# Xenon.net
KiCad netlist of a schematic drawn in Altium Designer
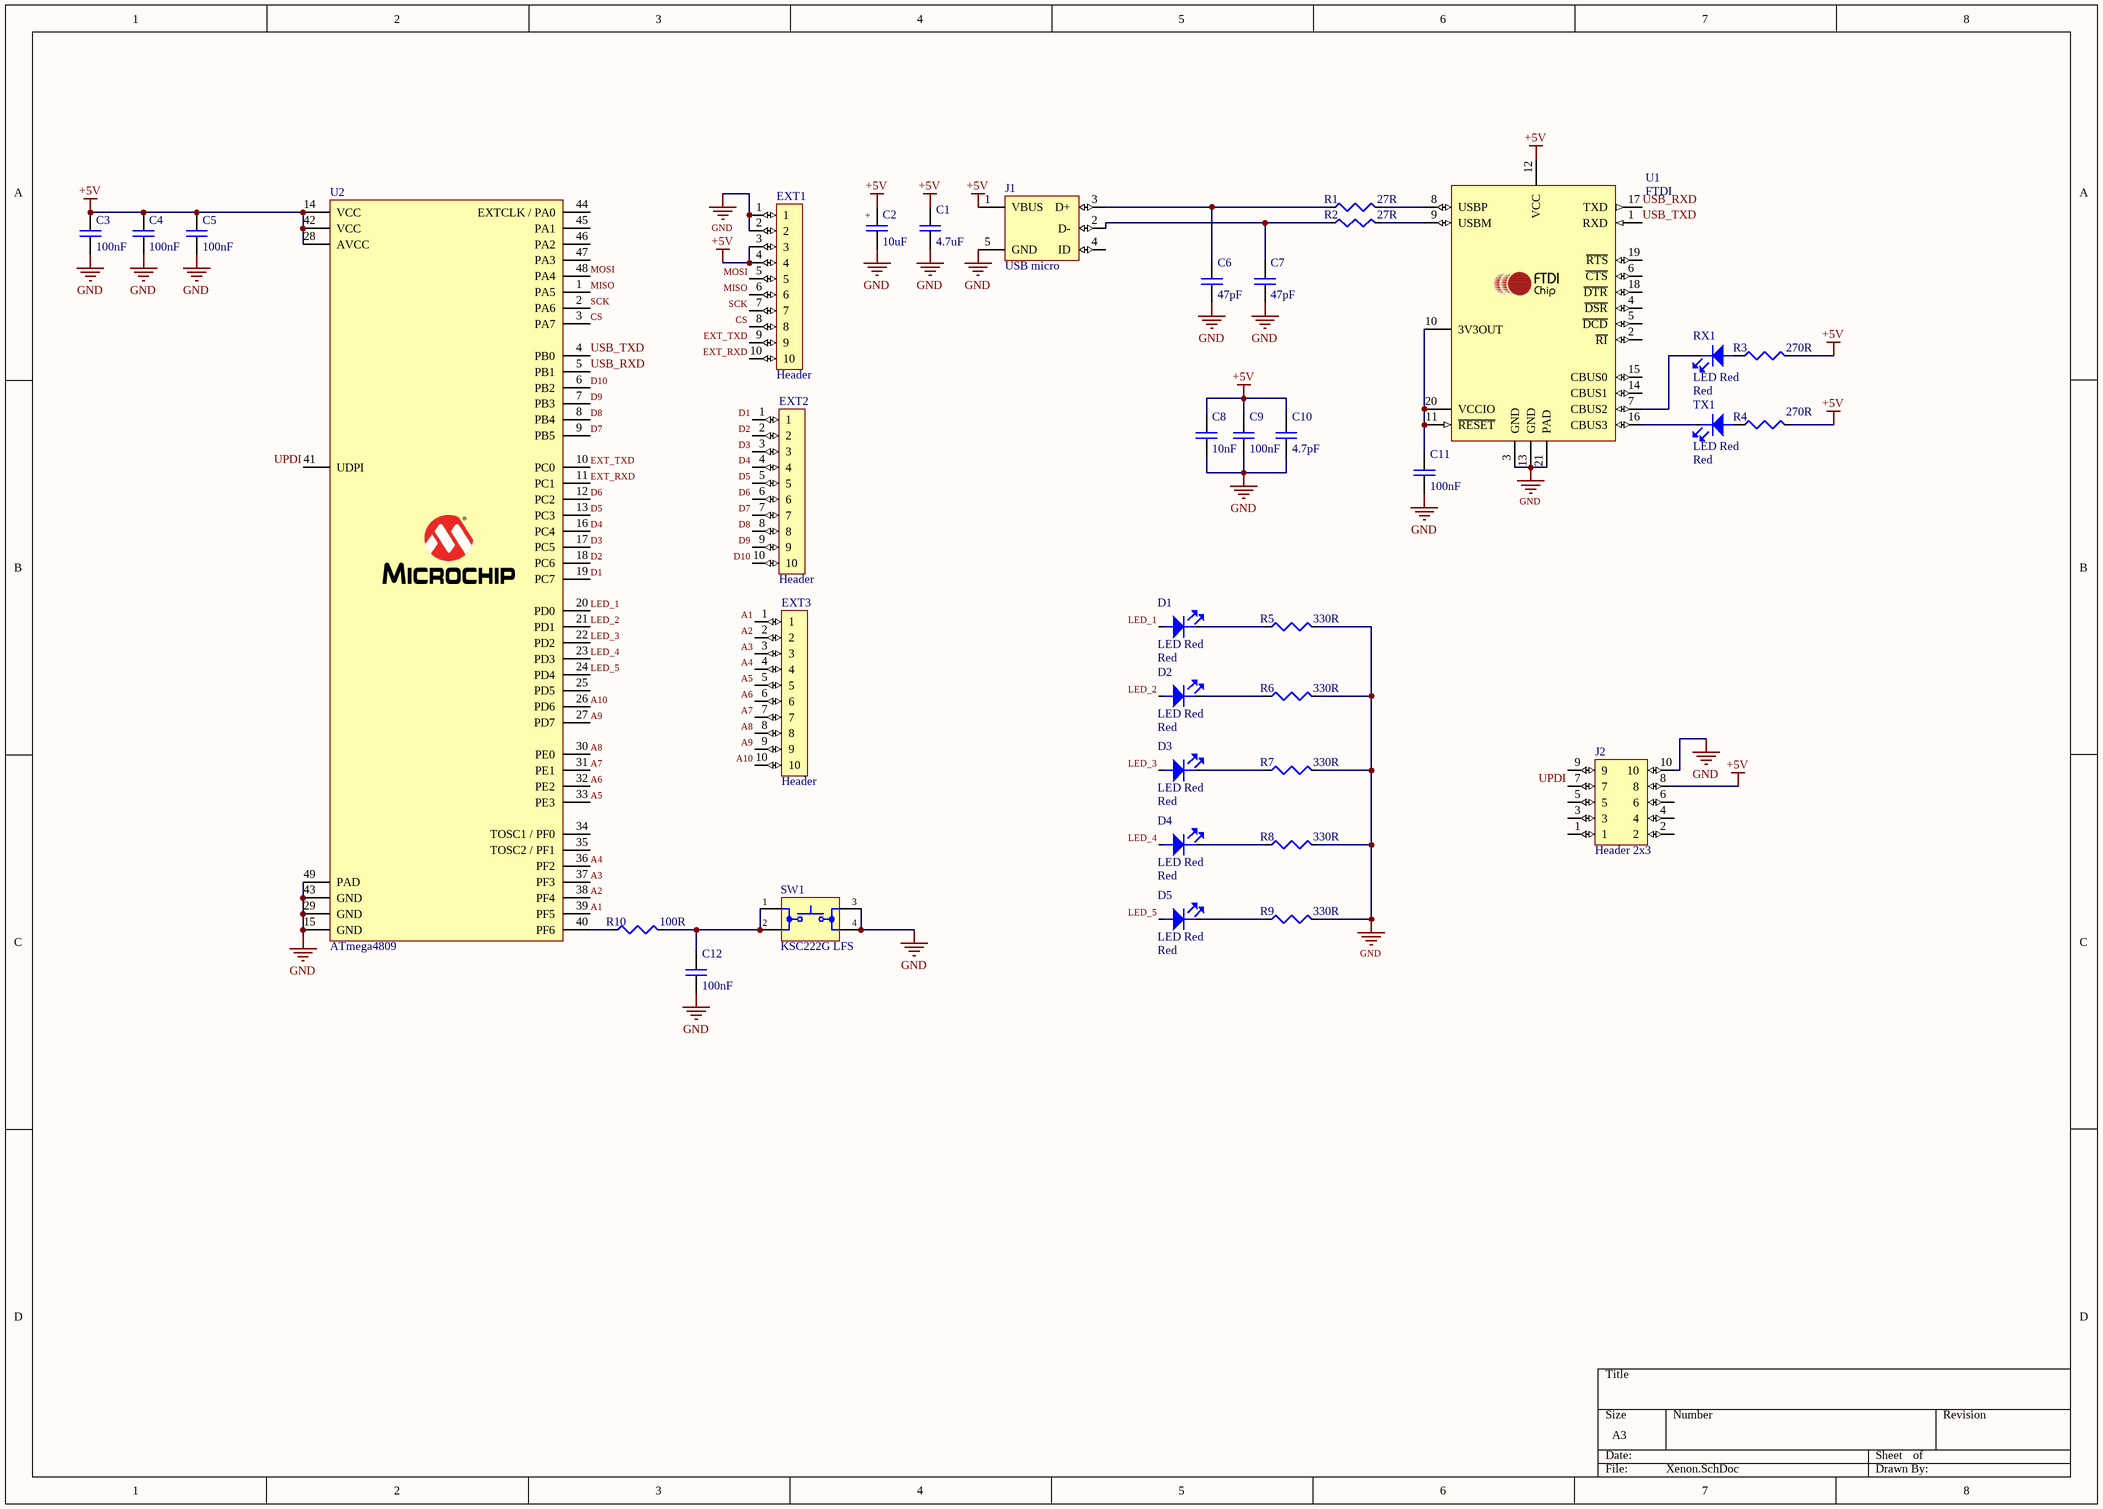
[diagram p0: Xenon.SchDoc]

(export (version "E")
  (design (tool "Eeschema 10.0.6"))
  (components
    (comp (ref "C1")
      (value "4.7uF")
      (footprint "C0603")
      (description "C0603")
      (fields (field (name "Comment") "02016D104KAT2A"))
      (libsource (lib "Passive components") (part "02016D104KAT2A"))
    )
    (comp (ref "C2")
      (value "10uF")
      (footprint "293D106X9020C2TE3")
      (description "Tant. CapasitorSMD 10uF")
      (fields (field (name "Comment") "293D106X9020C2TE3"))
      (libsource (lib "Passive components") (part "293D106X9020C2TE3"))
    )
    (comp (ref "C3")
      (value "100nF")
      (footprint "C0603")
      (description "C0603")
      (fields (field (name "Comment") "02016D104KAT2A"))
      (libsource (lib "Passive components") (part "02016D104KAT2A"))
    )
    (comp (ref "C4")
      (value "100nF")
      (footprint "C0603")
      (description "C0603")
      (fields (field (name "Comment") "02016D104KAT2A"))
      (libsource (lib "Passive components") (part "02016D104KAT2A"))
    )
    (comp (ref "C5")
      (value "100nF")
      (footprint "C0603")
      (description "C0603")
      (fields (field (name "Comment") "02016D104KAT2A"))
      (libsource (lib "Passive components") (part "02016D104KAT2A"))
    )
    (comp (ref "C6")
      (value "47pF")
      (footprint "C0603")
      (description "C0603")
      (fields (field (name "Comment") "02016D104KAT2A"))
      (libsource (lib "Passive components") (part "02016D104KAT2A"))
    )
    (comp (ref "C7")
      (value "47pF")
      (footprint "C0603")
      (description "C0603")
      (fields (field (name "Comment") "02016D104KAT2A"))
      (libsource (lib "Passive components") (part "02016D104KAT2A"))
    )
    (comp (ref "C8")
      (value "10nF")
      (footprint "C0603")
      (description "C0603")
      (fields (field (name "Comment") "02016D104KAT2A"))
      (libsource (lib "Passive components") (part "02016D104KAT2A"))
    )
    (comp (ref "C9")
      (value "100nF")
      (footprint "C0603")
      (description "C0603")
      (fields (field (name "Comment") "02016D104KAT2A"))
      (libsource (lib "Passive components") (part "02016D104KAT2A"))
    )
    (comp (ref "C10")
      (value "4.7pF")
      (footprint "C0603")
      (description "C0603")
      (fields (field (name "Comment") "02016D104KAT2A"))
      (libsource (lib "Passive components") (part "02016D104KAT2A"))
    )
    (comp (ref "C11")
      (value "100nF")
      (footprint "C0603")
      (description "C0603")
      (fields (field (name "Comment") "02016D104KAT2A"))
      (libsource (lib "Passive components") (part "02016D104KAT2A"))
    )
    (comp (ref "C12")
      (value "100nF")
      (footprint "C0603")
      (description "C0603")
      (fields (field (name "Comment") "02016D104KAT2A"))
      (libsource (lib "Passive components") (part "02016D104KAT2A"))
    )
    (comp (ref "D1")
      (value "LED Red")
      (footprint "L0603 RED")
      (description "LED 0603 Red")
      (fields (field (name "COLOR") "Red"))
      (libsource (lib "Passive components") (part "HSMG-C190"))
    )
    (comp (ref "D2")
      (value "LED Red")
      (footprint "L0603 RED")
      (description "LED 0603 Red")
      (fields (field (name "COLOR") "Red"))
      (libsource (lib "Passive components") (part "HSMG-C190"))
    )
    (comp (ref "D3")
      (value "LED Red")
      (footprint "L0603 RED")
      (description "LED 0603 Red")
      (fields (field (name "COLOR") "Red"))
      (libsource (lib "Passive components") (part "HSMG-C190"))
    )
    (comp (ref "D4")
      (value "LED Red")
      (footprint "L0603 RED")
      (description "LED 0603 Red")
      (fields (field (name "COLOR") "Red"))
      (libsource (lib "Passive components") (part "HSMG-C190"))
    )
    (comp (ref "D5")
      (value "LED Red")
      (footprint "L0603 RED")
      (description "LED 0603 Red")
      (fields (field (name "COLOR") "Red"))
      (libsource (lib "Passive components") (part "HSMG-C190"))
    )
    (comp (ref "EXT1")
      (value "Header")
      (footprint "Header 1x10 2.54mm")
      (description "Header 1x10 2.54mm male")
      (libsource (lib "Connectors") (part "2210S-10SG-85"))
    )
    (comp (ref "EXT2")
      (value "Header")
      (footprint "Header 1x10 2.54mm")
      (description "Header 1x10 2.54mm male")
      (libsource (lib "Connectors") (part "2210S-10SG-85"))
    )
    (comp (ref "EXT3")
      (value "Header")
      (footprint "Header 1x10 2.54mm")
      (description "Header 1x10 2.54mm male")
      (libsource (lib "Connectors") (part "2210S-10SG-85"))
    )
    (comp (ref "J1")
      (value "USB micro")
      (footprint "USB micro")
      (libsource (lib "Connectors") (part "47590-0001"))
    )
    (comp (ref "J2")
      (value "Header 2x3")
      (footprint "Header 2x5 1.27mm")
      (description "Header  2x5 1.27mm male")
      (libsource (lib "Connectors") (part "20021111-00010T4LF"))
    )
    (comp (ref "R1")
      (value "27R")
      (footprint "R0603")
      (description "R0603")
      (fields (field (name "Comment") "CPF-A-0603B100KE1"))
      (libsource (lib "Passive components") (part "CPF-A-0603B100KE1"))
    )
    (comp (ref "R2")
      (value "27R")
      (footprint "R0603")
      (description "R0603")
      (fields (field (name "Comment") "CPF-A-0603B100KE1"))
      (libsource (lib "Passive components") (part "CPF-A-0603B100KE1"))
    )
    (comp (ref "R3")
      (value "270R")
      (footprint "R0603")
      (description "R0603")
      (fields (field (name "Comment") "CPF-A-0603B100KE1"))
      (libsource (lib "Passive components") (part "CPF-A-0603B100KE1"))
    )
    (comp (ref "R4")
      (value "270R")
      (footprint "R0603")
      (description "R0603")
      (fields (field (name "Comment") "CPF-A-0603B100KE1"))
      (libsource (lib "Passive components") (part "CPF-A-0603B100KE1"))
    )
    (comp (ref "R5")
      (value "330R")
      (footprint "R0603")
      (description "R0603")
      (fields (field (name "Comment") "CPF-A-0603B100KE1"))
      (libsource (lib "Passive components") (part "CPF-A-0603B100KE1"))
    )
    (comp (ref "R6")
      (value "330R")
      (footprint "R0603")
      (description "R0603")
      (fields (field (name "Comment") "CPF-A-0603B100KE1"))
      (libsource (lib "Passive components") (part "CPF-A-0603B100KE1"))
    )
    (comp (ref "R7")
      (value "330R")
      (footprint "R0603")
      (description "R0603")
      (fields (field (name "Comment") "CPF-A-0603B100KE1"))
      (libsource (lib "Passive components") (part "CPF-A-0603B100KE1"))
    )
    (comp (ref "R8")
      (value "330R")
      (footprint "R0603")
      (description "R0603")
      (fields (field (name "Comment") "CPF-A-0603B100KE1"))
      (libsource (lib "Passive components") (part "CPF-A-0603B100KE1"))
    )
    (comp (ref "R9")
      (value "330R")
      (footprint "R0603")
      (description "R0603")
      (fields (field (name "Comment") "CPF-A-0603B100KE1"))
      (libsource (lib "Passive components") (part "CPF-A-0603B100KE1"))
    )
    (comp (ref "R10")
      (value "100R")
      (footprint "R0603")
      (description "R0603")
      (fields (field (name "Comment") "CPF-A-0603B100KE1"))
      (libsource (lib "Passive components") (part "CPF-A-0603B100KE1"))
    )
    (comp (ref "RX1")
      (value "LED Red")
      (footprint "L0603 RED")
      (description "LED 0603 Red")
      (fields (field (name "COLOR") "Red"))
      (libsource (lib "Passive components") (part "HSMG-C190"))
    )
    (comp (ref "SW1")
      (value "KSC222G LFS")
      (footprint "KSC222G LFS")
      (description "Button SMD")
      (libsource (lib "Sensors") (part "KSC222G LFS"))
    )
    (comp (ref "TX1")
      (value "LED Red")
      (footprint "L0603 RED")
      (description "LED 0603 Red")
      (fields (field (name "COLOR") "Red"))
      (libsource (lib "Passive components") (part "HSMG-C190"))
    )
    (comp (ref "U1")
      (value "FTDI")
      (footprint "FT231XQ-R")
      (description "UART to USB converter")
      (libsource (lib "IC") (part "FT231XQ-R"))
    )
    (comp (ref "U2")
      (value "ATmega4809")
      (footprint "ATMEGA4809-MFR")
      (description "ATmega4809 48-pin UQFN")
      (libsource (lib "Microcontrollers") (part "ATMEGA4809-MFR"))
    )
  )
  (nets
    (net (code "1") (name "+5V") (class "Default")
      (node (ref "C1") (pin "2") (pinfunction "2_2") (pintype "passive"))
      (node (ref "C10") (pin "2") (pinfunction "2_2") (pintype "passive"))
      (node (ref "C2") (pin "1") (pinfunction "1_1") (pintype "passive"))
      (node (ref "C3") (pin "2") (pinfunction "2_2") (pintype "passive"))
      (node (ref "C4") (pin "2") (pinfunction "2_2") (pintype "passive"))
      (node (ref "C5") (pin "2") (pinfunction "2_2") (pintype "passive"))
      (node (ref "C8") (pin "2") (pinfunction "2_2") (pintype "passive"))
      (node (ref "C9") (pin "2") (pinfunction "2_2") (pintype "passive"))
      (node (ref "EXT1") (pin "3") (pinfunction "3_3") (pintype "bidirectional"))
      (node (ref "EXT1") (pin "4") (pinfunction "4_4") (pintype "bidirectional"))
      (node (ref "J1") (pin "1") (pinfunction "VBUS_1") (pintype "passive"))
      (node (ref "J2") (pin "8") (pinfunction "8_8") (pintype "bidirectional"))
      (node (ref "R3") (pin "2") (pinfunction "2_2") (pintype "passive"))
      (node (ref "R4") (pin "2") (pinfunction "2_2") (pintype "passive"))
      (node (ref "U1") (pin "12") (pinfunction "VCC_12") (pintype "passive"))
      (node (ref "U2") (pin "14") (pinfunction "VCC_14") (pintype "passive"))
      (node (ref "U2") (pin "28") (pinfunction "AVCC_28") (pintype "passive"))
      (node (ref "U2") (pin "42") (pinfunction "VCC_42") (pintype "passive"))
    )
    (net (code "2") (name "/A1") (class "Default")
      (node (ref "EXT3") (pin "1") (pinfunction "1_1") (pintype "bidirectional"))
      (node (ref "U2") (pin "39") (pinfunction "PF5_39") (pintype "passive"))
    )
    (net (code "3") (name "/A2") (class "Default")
      (node (ref "EXT3") (pin "2") (pinfunction "2_2") (pintype "bidirectional"))
      (node (ref "U2") (pin "38") (pinfunction "PF4_38") (pintype "passive"))
    )
    (net (code "4") (name "/A3") (class "Default")
      (node (ref "EXT3") (pin "3") (pinfunction "3_3") (pintype "bidirectional"))
      (node (ref "U2") (pin "37") (pinfunction "PF3_37") (pintype "passive"))
    )
    (net (code "5") (name "/A4") (class "Default")
      (node (ref "EXT3") (pin "4") (pinfunction "4_4") (pintype "bidirectional"))
      (node (ref "U2") (pin "36") (pinfunction "PF2_36") (pintype "passive"))
    )
    (net (code "6") (name "/A5") (class "Default")
      (node (ref "EXT3") (pin "5") (pinfunction "5_5") (pintype "bidirectional"))
      (node (ref "U2") (pin "33") (pinfunction "PE3_33") (pintype "passive"))
    )
    (net (code "7") (name "/A6") (class "Default")
      (node (ref "EXT3") (pin "6") (pinfunction "6_6") (pintype "bidirectional"))
      (node (ref "U2") (pin "32") (pinfunction "PE2_32") (pintype "passive"))
    )
    (net (code "8") (name "/A7") (class "Default")
      (node (ref "EXT3") (pin "7") (pinfunction "7_7") (pintype "bidirectional"))
      (node (ref "U2") (pin "31") (pinfunction "PE1_31") (pintype "passive"))
    )
    (net (code "9") (name "/A8") (class "Default")
      (node (ref "EXT3") (pin "8") (pinfunction "8_8") (pintype "bidirectional"))
      (node (ref "U2") (pin "30") (pinfunction "PE0_30") (pintype "passive"))
    )
    (net (code "10") (name "/A9") (class "Default")
      (node (ref "EXT3") (pin "9") (pinfunction "9_9") (pintype "bidirectional"))
      (node (ref "U2") (pin "27") (pinfunction "PD7_27") (pintype "passive"))
    )
    (net (code "11") (name "/A10") (class "Default")
      (node (ref "EXT3") (pin "10") (pinfunction "10_10") (pintype "bidirectional"))
      (node (ref "U2") (pin "26") (pinfunction "PD6_26") (pintype "passive"))
    )
    (net (code "12") (name "/CS") (class "Default")
      (node (ref "EXT1") (pin "8") (pinfunction "8_8") (pintype "bidirectional"))
      (node (ref "U2") (pin "3") (pinfunction "PA7_3") (pintype "passive"))
    )
    (net (code "13") (name "/D1") (class "Default")
      (node (ref "EXT2") (pin "1") (pinfunction "1_1") (pintype "bidirectional"))
      (node (ref "U2") (pin "19") (pinfunction "PC7_19") (pintype "passive"))
    )
    (net (code "14") (name "/D2") (class "Default")
      (node (ref "EXT2") (pin "2") (pinfunction "2_2") (pintype "bidirectional"))
      (node (ref "U2") (pin "18") (pinfunction "PC6_18") (pintype "passive"))
    )
    (net (code "15") (name "/D3") (class "Default")
      (node (ref "EXT2") (pin "3") (pinfunction "3_3") (pintype "bidirectional"))
      (node (ref "U2") (pin "17") (pinfunction "PC5_17") (pintype "passive"))
    )
    (net (code "16") (name "/D4") (class "Default")
      (node (ref "EXT2") (pin "4") (pinfunction "4_4") (pintype "bidirectional"))
      (node (ref "U2") (pin "16") (pinfunction "PC4_16") (pintype "passive"))
    )
    (net (code "17") (name "/D5") (class "Default")
      (node (ref "EXT2") (pin "5") (pinfunction "5_5") (pintype "bidirectional"))
      (node (ref "U2") (pin "13") (pinfunction "PC3_13") (pintype "passive"))
    )
    (net (code "18") (name "/D6") (class "Default")
      (node (ref "EXT2") (pin "6") (pinfunction "6_6") (pintype "bidirectional"))
      (node (ref "U2") (pin "12") (pinfunction "PC2_12") (pintype "passive"))
    )
    (net (code "19") (name "/D7") (class "Default")
      (node (ref "EXT2") (pin "7") (pinfunction "7_7") (pintype "bidirectional"))
      (node (ref "U2") (pin "9") (pinfunction "PB5_9") (pintype "passive"))
    )
    (net (code "20") (name "/D8") (class "Default")
      (node (ref "EXT2") (pin "8") (pinfunction "8_8") (pintype "bidirectional"))
      (node (ref "U2") (pin "8") (pinfunction "PB4_8") (pintype "passive"))
    )
    (net (code "21") (name "/D9") (class "Default")
      (node (ref "EXT2") (pin "9") (pinfunction "9_9") (pintype "bidirectional"))
      (node (ref "U2") (pin "7") (pinfunction "PB3_7") (pintype "passive"))
    )
    (net (code "22") (name "/D10") (class "Default")
      (node (ref "EXT2") (pin "10") (pinfunction "10_10") (pintype "bidirectional"))
      (node (ref "U2") (pin "6") (pinfunction "PB2_6") (pintype "passive"))
    )
    (net (code "23") (name "/EXT_RXD") (class "Default")
      (node (ref "EXT1") (pin "10") (pinfunction "10_10") (pintype "bidirectional"))
      (node (ref "U2") (pin "11") (pinfunction "PC1_11") (pintype "passive"))
    )
    (net (code "24") (name "/EXT_TXD") (class "Default")
      (node (ref "EXT1") (pin "9") (pinfunction "9_9") (pintype "bidirectional"))
      (node (ref "U2") (pin "10") (pinfunction "PC0_10") (pintype "passive"))
    )
    (net (code "25") (name "/LED_1") (class "Default")
      (node (ref "D1") (pin "1") (pinfunction "1_1") (pintype "passive"))
      (node (ref "U2") (pin "20") (pinfunction "PD0_20") (pintype "passive"))
    )
    (net (code "26") (name "/LED_2") (class "Default")
      (node (ref "D2") (pin "1") (pinfunction "1_1") (pintype "passive"))
      (node (ref "U2") (pin "21") (pinfunction "PD1_21") (pintype "passive"))
    )
    (net (code "27") (name "/LED_3") (class "Default")
      (node (ref "D3") (pin "1") (pinfunction "1_1") (pintype "passive"))
      (node (ref "U2") (pin "22") (pinfunction "PD2_22") (pintype "passive"))
    )
    (net (code "28") (name "/LED_4") (class "Default")
      (node (ref "D4") (pin "1") (pinfunction "1_1") (pintype "passive"))
      (node (ref "U2") (pin "23") (pinfunction "PD3_23") (pintype "passive"))
    )
    (net (code "29") (name "/LED_5") (class "Default")
      (node (ref "D5") (pin "1") (pinfunction "1_1") (pintype "passive"))
      (node (ref "U2") (pin "24") (pinfunction "PD4_24") (pintype "passive"))
    )
    (net (code "30") (name "/MISO") (class "Default")
      (node (ref "EXT1") (pin "6") (pinfunction "6_6") (pintype "bidirectional"))
      (node (ref "U2") (pin "1") (pinfunction "PA5_1") (pintype "passive"))
    )
    (net (code "31") (name "/MOSI") (class "Default")
      (node (ref "EXT1") (pin "5") (pinfunction "5_5") (pintype "bidirectional"))
      (node (ref "U2") (pin "48") (pinfunction "PA4_48") (pintype "passive"))
    )
    (net (code "32") (name "/SCK") (class "Default")
      (node (ref "EXT1") (pin "7") (pinfunction "7_7") (pintype "bidirectional"))
      (node (ref "U2") (pin "2") (pinfunction "PA6_2") (pintype "passive"))
    )
    (net (code "33") (name "/UPDI") (class "Default")
      (node (ref "J2") (pin "7") (pinfunction "7_7") (pintype "bidirectional"))
      (node (ref "U2") (pin "41") (pinfunction "UDPI_41") (pintype "passive"))
    )
    (net (code "34") (name "/USB_RXD") (class "Default")
      (node (ref "U1") (pin "17") (pinfunction "TXD_17") (pintype "output"))
      (node (ref "U2") (pin "5") (pinfunction "PB1_5") (pintype "passive"))
    )
    (net (code "35") (name "/USB_TXD") (class "Default")
      (node (ref "U1") (pin "1") (pinfunction "RXD_1") (pintype "input"))
      (node (ref "U2") (pin "4") (pinfunction "PB0_4") (pintype "passive"))
    )
    (net (code "36") (name "GND") (class "Default")
      (node (ref "C1") (pin "1") (pinfunction "1_1") (pintype "passive"))
      (node (ref "C10") (pin "1") (pinfunction "1_1") (pintype "passive"))
      (node (ref "C11") (pin "1") (pinfunction "1_1") (pintype "passive"))
      (node (ref "C12") (pin "1") (pinfunction "1_1") (pintype "passive"))
      (node (ref "C2") (pin "2") (pinfunction "2_2") (pintype "passive"))
      (node (ref "C3") (pin "1") (pinfunction "1_1") (pintype "passive"))
      (node (ref "C4") (pin "1") (pinfunction "1_1") (pintype "passive"))
      (node (ref "C5") (pin "1") (pinfunction "1_1") (pintype "passive"))
      (node (ref "C6") (pin "1") (pinfunction "1_1") (pintype "passive"))
      (node (ref "C7") (pin "1") (pinfunction "1_1") (pintype "passive"))
      (node (ref "C8") (pin "1") (pinfunction "1_1") (pintype "passive"))
      (node (ref "C9") (pin "1") (pinfunction "1_1") (pintype "passive"))
      (node (ref "EXT1") (pin "1") (pinfunction "1_1") (pintype "bidirectional"))
      (node (ref "EXT1") (pin "2") (pinfunction "2_2") (pintype "bidirectional"))
      (node (ref "J1") (pin "5") (pinfunction "GND_5") (pintype "passive"))
      (node (ref "J2") (pin "10") (pinfunction "10_10") (pintype "bidirectional"))
      (node (ref "R5") (pin "2") (pinfunction "2_2") (pintype "passive"))
      (node (ref "R6") (pin "2") (pinfunction "2_2") (pintype "passive"))
      (node (ref "R7") (pin "2") (pinfunction "2_2") (pintype "passive"))
      (node (ref "R8") (pin "2") (pinfunction "2_2") (pintype "passive"))
      (node (ref "R9") (pin "2") (pinfunction "2_2") (pintype "passive"))
      (node (ref "SW1") (pin "3") (pinfunction "3_3") (pintype "passive"))
      (node (ref "SW1") (pin "4") (pinfunction "4_4") (pintype "passive"))
      (node (ref "U1") (pin "13") (pinfunction "GND_13") (pintype "passive"))
      (node (ref "U1") (pin "21") (pinfunction "PAD_21") (pintype "passive"))
      (node (ref "U1") (pin "3") (pinfunction "GND_3") (pintype "passive"))
      (node (ref "U2") (pin "15") (pinfunction "GND_15") (pintype "passive"))
      (node (ref "U2") (pin "29") (pinfunction "GND_29") (pintype "passive"))
      (node (ref "U2") (pin "43") (pinfunction "GND_43") (pintype "passive"))
      (node (ref "U2") (pin "49") (pinfunction "PAD_49") (pintype "passive"))
    )
    (net (code "37") (name "Net-(C12-Pad2)") (class "Default")
      (node (ref "C12") (pin "2") (pinfunction "2_2") (pintype "passive"))
      (node (ref "R10") (pin "2") (pinfunction "2_2") (pintype "passive"))
      (node (ref "SW1") (pin "1") (pinfunction "1_1") (pintype "passive"))
      (node (ref "SW1") (pin "2") (pinfunction "2_2") (pintype "passive"))
    )
    (net (code "38") (name "Net-(D1-Pad2)") (class "Default")
      (node (ref "D1") (pin "2") (pinfunction "2_2") (pintype "passive"))
      (node (ref "R5") (pin "1") (pinfunction "1_1") (pintype "passive"))
    )
    (net (code "39") (name "Net-(D2-Pad2)") (class "Default")
      (node (ref "D2") (pin "2") (pinfunction "2_2") (pintype "passive"))
      (node (ref "R6") (pin "1") (pinfunction "1_1") (pintype "passive"))
    )
    (net (code "40") (name "Net-(D3-Pad2)") (class "Default")
      (node (ref "D3") (pin "2") (pinfunction "2_2") (pintype "passive"))
      (node (ref "R7") (pin "1") (pinfunction "1_1") (pintype "passive"))
    )
    (net (code "41") (name "Net-(D4-Pad2)") (class "Default")
      (node (ref "D4") (pin "2") (pinfunction "2_2") (pintype "passive"))
      (node (ref "R8") (pin "1") (pinfunction "1_1") (pintype "passive"))
    )
    (net (code "42") (name "Net-(D5-Pad2)") (class "Default")
      (node (ref "D5") (pin "2") (pinfunction "2_2") (pintype "passive"))
      (node (ref "R9") (pin "1") (pinfunction "1_1") (pintype "passive"))
    )
    (net (code "43") (name "Net-(J1-D+)") (class "Default")
      (node (ref "C6") (pin "2") (pinfunction "2_2") (pintype "passive"))
      (node (ref "J1") (pin "3") (pinfunction "D+_3") (pintype "bidirectional"))
      (node (ref "R1") (pin "1") (pinfunction "1_1") (pintype "passive"))
    )
    (net (code "44") (name "Net-(J1-D-)") (class "Default")
      (node (ref "C7") (pin "2") (pinfunction "2_2") (pintype "passive"))
      (node (ref "J1") (pin "2") (pinfunction "D-_2") (pintype "bidirectional"))
      (node (ref "R2") (pin "1") (pinfunction "1_1") (pintype "passive"))
    )
    (net (code "45") (name "Net-(R3-Pad1)") (class "Default")
      (node (ref "R3") (pin "1") (pinfunction "1_1") (pintype "passive"))
      (node (ref "RX1") (pin "1") (pinfunction "1_1") (pintype "passive"))
    )
    (net (code "46") (name "Net-(R4-Pad1)") (class "Default")
      (node (ref "R4") (pin "1") (pinfunction "1_1") (pintype "passive"))
      (node (ref "TX1") (pin "1") (pinfunction "1_1") (pintype "passive"))
    )
    (net (code "47") (name "Net-(U1-3V3OUT)") (class "Default")
      (node (ref "C11") (pin "2") (pinfunction "2_2") (pintype "passive"))
      (node (ref "U1") (pin "10") (pinfunction "3V3OUT_10") (pintype "passive"))
      (node (ref "U1") (pin "11") (pinfunction "~{RESET}_11") (pintype "input"))
      (node (ref "U1") (pin "20") (pinfunction "VCCIO_20") (pintype "passive"))
    )
    (net (code "48") (name "Net-(U1-CBUS2)") (class "Default")
      (node (ref "RX1") (pin "2") (pinfunction "2_2") (pintype "passive"))
      (node (ref "U1") (pin "7") (pinfunction "CBUS2_7") (pintype "bidirectional"))
    )
    (net (code "49") (name "Net-(U1-CBUS3)") (class "Default")
      (node (ref "TX1") (pin "2") (pinfunction "2_2") (pintype "passive"))
      (node (ref "U1") (pin "16") (pinfunction "CBUS3_16") (pintype "bidirectional"))
    )
    (net (code "50") (name "Net-(U1-USBM)") (class "Default")
      (node (ref "R2") (pin "2") (pinfunction "2_2") (pintype "passive"))
      (node (ref "U1") (pin "9") (pinfunction "USBM_9") (pintype "bidirectional"))
    )
    (net (code "51") (name "Net-(U1-USBP)") (class "Default")
      (node (ref "R1") (pin "2") (pinfunction "2_2") (pintype "passive"))
      (node (ref "U1") (pin "8") (pinfunction "USBP_8") (pintype "bidirectional"))
    )
    (net (code "52") (name "Net-(U2-PF6)") (class "Default")
      (node (ref "R10") (pin "1") (pinfunction "1_1") (pintype "passive"))
      (node (ref "U2") (pin "40") (pinfunction "PF6_40") (pintype "passive"))
    )
    (net (code "53") (name "unconnected-(J1-ID-Pad4)") (class "Default")
      (node (ref "J1") (pin "4") (pinfunction "ID_4") (pintype "bidirectional"))
    )
    (net (code "54") (name "unconnected-(J2-Pad1)") (class "Default")
      (node (ref "J2") (pin "1") (pinfunction "1_1") (pintype "bidirectional"))
    )
    (net (code "55") (name "unconnected-(J2-Pad2)") (class "Default")
      (node (ref "J2") (pin "2") (pinfunction "2_2") (pintype "bidirectional"))
    )
    (net (code "56") (name "unconnected-(J2-Pad3)") (class "Default")
      (node (ref "J2") (pin "3") (pinfunction "3_3") (pintype "bidirectional"))
    )
    (net (code "57") (name "unconnected-(J2-Pad4)") (class "Default")
      (node (ref "J2") (pin "4") (pinfunction "4_4") (pintype "bidirectional"))
    )
    (net (code "58") (name "unconnected-(J2-Pad5)") (class "Default")
      (node (ref "J2") (pin "5") (pinfunction "5_5") (pintype "bidirectional"))
    )
    (net (code "59") (name "unconnected-(J2-Pad6)") (class "Default")
      (node (ref "J2") (pin "6") (pinfunction "6_6") (pintype "bidirectional"))
    )
    (net (code "60") (name "unconnected-(J2-Pad9)") (class "Default")
      (node (ref "J2") (pin "9") (pinfunction "9_9") (pintype "bidirectional"))
    )
    (net (code "61") (name "unconnected-(U1-CBUS0-Pad15)") (class "Default")
      (node (ref "U1") (pin "15") (pinfunction "CBUS0_15") (pintype "bidirectional"))
    )
    (net (code "62") (name "unconnected-(U1-CBUS1-Pad14)") (class "Default")
      (node (ref "U1") (pin "14") (pinfunction "CBUS1_14") (pintype "bidirectional"))
    )
    (net (code "63") (name "unconnected-(U1-~{CTS}-Pad6)") (class "Default")
      (node (ref "U1") (pin "6") (pinfunction "~{CTS}_6") (pintype "bidirectional"))
    )
    (net (code "64") (name "unconnected-(U1-~{DCD}-Pad5)") (class "Default")
      (node (ref "U1") (pin "5") (pinfunction "~{DCD}_5") (pintype "bidirectional"))
    )
    (net (code "65") (name "unconnected-(U1-~{DSR}-Pad4)") (class "Default")
      (node (ref "U1") (pin "4") (pinfunction "~{DSR}_4") (pintype "bidirectional"))
    )
    (net (code "66") (name "unconnected-(U1-~{DTR}-Pad18)") (class "Default")
      (node (ref "U1") (pin "18") (pinfunction "~{DTR}_18") (pintype "bidirectional"))
    )
    (net (code "67") (name "unconnected-(U1-~{RI}-Pad2)") (class "Default")
      (node (ref "U1") (pin "2") (pinfunction "~{RI}_2") (pintype "bidirectional"))
    )
    (net (code "68") (name "unconnected-(U1-~{RTS}-Pad19)") (class "Default")
      (node (ref "U1") (pin "19") (pinfunction "~{RTS}_19") (pintype "bidirectional"))
    )
    (net (code "69") (name "unconnected-(U2-EXTCLK_{slash}_PA0-Pad44)") (class "Default")
      (node (ref "U2") (pin "44") (pinfunction "EXTCLK_/_PA0_44") (pintype "passive"))
    )
    (net (code "70") (name "unconnected-(U2-PA1-Pad45)") (class "Default")
      (node (ref "U2") (pin "45") (pinfunction "PA1_45") (pintype "passive"))
    )
    (net (code "71") (name "unconnected-(U2-PA2-Pad46)") (class "Default")
      (node (ref "U2") (pin "46") (pinfunction "PA2_46") (pintype "passive"))
    )
    (net (code "72") (name "unconnected-(U2-PA3-Pad47)") (class "Default")
      (node (ref "U2") (pin "47") (pinfunction "PA3_47") (pintype "passive"))
    )
    (net (code "73") (name "unconnected-(U2-PD5-Pad25)") (class "Default")
      (node (ref "U2") (pin "25") (pinfunction "PD5_25") (pintype "passive"))
    )
    (net (code "74") (name "unconnected-(U2-TOSC1_{slash}_PF0-Pad34)") (class "Default")
      (node (ref "U2") (pin "34") (pinfunction "TOSC1_/_PF0_34") (pintype "passive"))
    )
    (net (code "75") (name "unconnected-(U2-TOSC2_{slash}_PF1-Pad35)") (class "Default")
      (node (ref "U2") (pin "35") (pinfunction "TOSC2_/_PF1_35") (pintype "passive"))
    )
  )
)
